# led_board.net
KiCad netlist of a schematic drawn in EAGLE
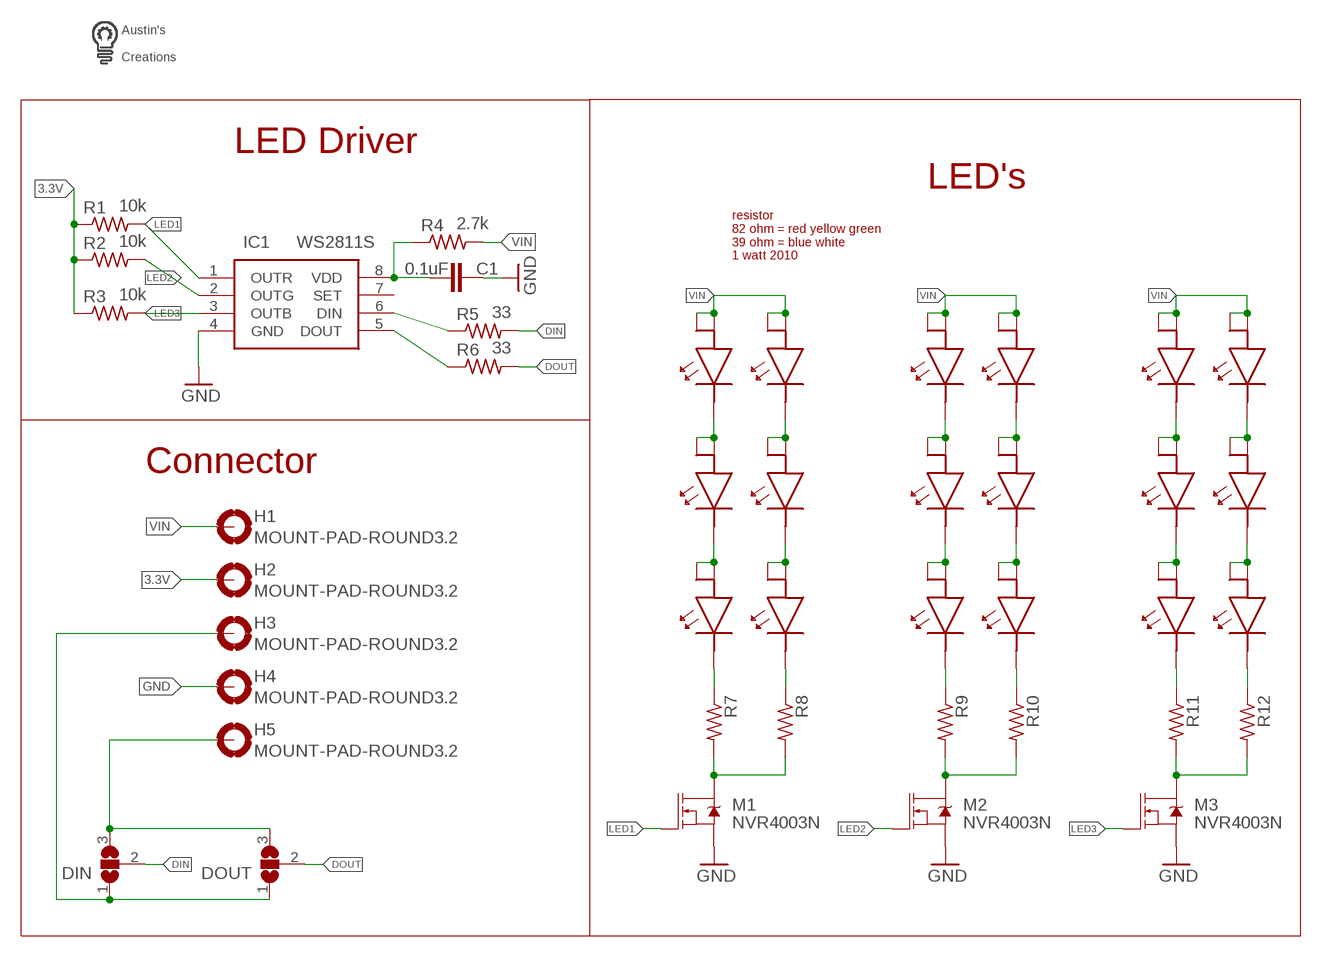
[diagram p0: schematic, sheet 1]

(export (version "E")
  (design (tool "Eeschema 10.0.6"))
  (components
    (comp (ref "C1")
      (value "0.1uF")
      (footprint "eagle-import:C0603K")
      (libsource (lib "eagle-import") (part "C-EUC0603K"))
    )
    (comp (ref "DIN")
      (value "SJ2WW")
      (footprint "eagle-import:SJ_2W")
      (libsource (lib "eagle-import") (part "SJ2WW"))
    )
    (comp (ref "DOUT")
      (value "SJ2WW")
      (footprint "eagle-import:SJ_2W")
      (libsource (lib "eagle-import") (part "SJ2WW"))
    )
    (comp (ref "H1")
      (value "MOUNT-PAD-ROUND3.2")
      (footprint "eagle-import:3,2-PAD")
      (libsource (lib "eagle-import") (part "MOUNT-PAD-ROUND3.2"))
    )
    (comp (ref "H2")
      (value "MOUNT-PAD-ROUND3.2")
      (footprint "eagle-import:3,2-PAD")
      (libsource (lib "eagle-import") (part "MOUNT-PAD-ROUND3.2"))
    )
    (comp (ref "H3")
      (value "MOUNT-PAD-ROUND3.2")
      (footprint "eagle-import:3,2-PAD")
      (libsource (lib "eagle-import") (part "MOUNT-PAD-ROUND3.2"))
    )
    (comp (ref "H4")
      (value "MOUNT-PAD-ROUND3.2")
      (footprint "eagle-import:3,2-PAD")
      (libsource (lib "eagle-import") (part "MOUNT-PAD-ROUND3.2"))
    )
    (comp (ref "H5")
      (value "MOUNT-PAD-ROUND3.2")
      (footprint "eagle-import:3,2-PAD")
      (libsource (lib "eagle-import") (part "MOUNT-PAD-ROUND3.2"))
    )
    (comp (ref "IC1")
      (value "WS2811S")
      (footprint "eagle-import:SOIC127P600X175-8N")
      (fields (field (name "MANUFACTURER_PART_NUMBER") "ws2811s"))
      (libsource (lib "eagle-import") (part "WS2811S"))
    )
    (comp (ref "L1")
      (value "5730LED")
      (footprint "eagle-import:5730LED")
      (libsource (lib "eagle-import") (part "5730LED"))
    )
    (comp (ref "L2")
      (value "5730LED")
      (footprint "eagle-import:5730LED")
      (libsource (lib "eagle-import") (part "5730LED"))
    )
    (comp (ref "L3")
      (value "5730LED")
      (footprint "eagle-import:5730LED")
      (libsource (lib "eagle-import") (part "5730LED"))
    )
    (comp (ref "L4")
      (value "5730LED")
      (footprint "eagle-import:5730LED")
      (libsource (lib "eagle-import") (part "5730LED"))
    )
    (comp (ref "L5")
      (value "5730LED")
      (footprint "eagle-import:5730LED")
      (libsource (lib "eagle-import") (part "5730LED"))
    )
    (comp (ref "L6")
      (value "5730LED")
      (footprint "eagle-import:5730LED")
      (libsource (lib "eagle-import") (part "5730LED"))
    )
    (comp (ref "L7")
      (value "5730LED")
      (footprint "eagle-import:5730LED")
      (libsource (lib "eagle-import") (part "5730LED"))
    )
    (comp (ref "L8")
      (value "5730LED")
      (footprint "eagle-import:5730LED")
      (libsource (lib "eagle-import") (part "5730LED"))
    )
    (comp (ref "L9")
      (value "5730LED")
      (footprint "eagle-import:5730LED")
      (libsource (lib "eagle-import") (part "5730LED"))
    )
    (comp (ref "L10")
      (value "5730LED")
      (footprint "eagle-import:5730LED")
      (libsource (lib "eagle-import") (part "5730LED"))
    )
    (comp (ref "L11")
      (value "5730LED")
      (footprint "eagle-import:5730LED")
      (libsource (lib "eagle-import") (part "5730LED"))
    )
    (comp (ref "L12")
      (value "5730LED")
      (footprint "eagle-import:5730LED")
      (libsource (lib "eagle-import") (part "5730LED"))
    )
    (comp (ref "L13")
      (value "5730LED")
      (footprint "eagle-import:5730LED")
      (libsource (lib "eagle-import") (part "5730LED"))
    )
    (comp (ref "L14")
      (value "5730LED")
      (footprint "eagle-import:5730LED")
      (libsource (lib "eagle-import") (part "5730LED"))
    )
    (comp (ref "L15")
      (value "5730LED")
      (footprint "eagle-import:5730LED")
      (libsource (lib "eagle-import") (part "5730LED"))
    )
    (comp (ref "L16")
      (value "5730LED")
      (footprint "eagle-import:5730LED")
      (libsource (lib "eagle-import") (part "5730LED"))
    )
    (comp (ref "L17")
      (value "5730LED")
      (footprint "eagle-import:5730LED")
      (libsource (lib "eagle-import") (part "5730LED"))
    )
    (comp (ref "L18")
      (value "5730LED")
      (footprint "eagle-import:5730LED")
      (libsource (lib "eagle-import") (part "5730LED"))
    )
    (comp (ref "M1")
      (value "NVR4003N")
      (footprint "eagle-import:SOT23")
      (libsource (lib "eagle-import") (part "NVR4003N"))
    )
    (comp (ref "M2")
      (value "NVR4003N")
      (footprint "eagle-import:SOT23")
      (libsource (lib "eagle-import") (part "NVR4003N"))
    )
    (comp (ref "M3")
      (value "NVR4003N")
      (footprint "eagle-import:SOT23")
      (libsource (lib "eagle-import") (part "NVR4003N"))
    )
    (comp (ref "R1")
      (value "10k")
      (footprint "eagle-import:R0603")
      (libsource (lib "eagle-import") (part "resistor_348_R-US_R0603"))
    )
    (comp (ref "R2")
      (value "10k")
      (footprint "eagle-import:R0603")
      (libsource (lib "eagle-import") (part "resistor_348_R-US_R0603"))
    )
    (comp (ref "R3")
      (value "10k")
      (footprint "eagle-import:R0603")
      (libsource (lib "eagle-import") (part "resistor_348_R-US_R0603"))
    )
    (comp (ref "R4")
      (value "2.7k")
      (footprint "eagle-import:R0603")
      (libsource (lib "eagle-import") (part "resistor_348_R-US_R0603"))
    )
    (comp (ref "R5")
      (value "33")
      (footprint "eagle-import:R0603")
      (libsource (lib "eagle-import") (part "resistor_348_R-US_R0603"))
    )
    (comp (ref "R6")
      (value "33")
      (footprint "eagle-import:R0603")
      (libsource (lib "eagle-import") (part "resistor_348_R-US_R0603"))
    )
    (comp (ref "R7")
      (value "R-US_R2010")
      (footprint "eagle-import:R2010")
      (libsource (lib "eagle-import") (part "R-US_R2010"))
    )
    (comp (ref "R8")
      (value "R-US_R2010")
      (footprint "eagle-import:R2010")
      (libsource (lib "eagle-import") (part "R-US_R2010"))
    )
    (comp (ref "R9")
      (value "R-US_R2010")
      (footprint "eagle-import:R2010")
      (libsource (lib "eagle-import") (part "R-US_R2010"))
    )
    (comp (ref "R10")
      (value "R-US_R2010")
      (footprint "eagle-import:R2010")
      (libsource (lib "eagle-import") (part "R-US_R2010"))
    )
    (comp (ref "R11")
      (value "R-US_R2010")
      (footprint "eagle-import:R2010")
      (libsource (lib "eagle-import") (part "R-US_R2010"))
    )
    (comp (ref "R12")
      (value "R-US_R2010")
      (footprint "eagle-import:R2010")
      (libsource (lib "eagle-import") (part "R-US_R2010"))
    )
    (comp (ref "U$2")
      (value "LOGO")
      (footprint "eagle-import:LOGO")
      (libsource (lib "eagle-import") (part "LOGO"))
    )
  )
  (nets
    (net (code "1") (name "3.3V") (class "Default")
      (node (ref "H2") (pin "B3,2") (pinfunction "MOUNT_B3,2") (pintype "passive"))
      (node (ref "R1") (pin "1") (pinfunction "1_1") (pintype "passive"))
      (node (ref "R2") (pin "1") (pinfunction "1_1") (pintype "passive"))
      (node (ref "R3") (pin "1") (pinfunction "1_1") (pintype "passive"))
    )
    (net (code "2") (name "DIN") (class "Default")
      (node (ref "DIN") (pin "2") (pinfunction "2_2") (pintype "passive"))
      (node (ref "R5") (pin "2") (pinfunction "2_2") (pintype "passive"))
    )
    (net (code "3") (name "DOUT") (class "Default")
      (node (ref "DOUT") (pin "2") (pinfunction "2_2") (pintype "passive"))
      (node (ref "R6") (pin "2") (pinfunction "2_2") (pintype "passive"))
    )
    (net (code "4") (name "GND") (class "Default")
      (node (ref "C1") (pin "1") (pinfunction "1_1") (pintype "passive"))
      (node (ref "H4") (pin "B3,2") (pinfunction "MOUNT_B3,2") (pintype "passive"))
      (node (ref "IC1") (pin "4") (pinfunction "GND_4") (pintype "power_in"))
      (node (ref "M1") (pin "3") (pinfunction "S_3") (pintype "bidirectional"))
      (node (ref "M2") (pin "3") (pinfunction "S_3") (pintype "bidirectional"))
      (node (ref "M3") (pin "3") (pinfunction "S_3") (pintype "bidirectional"))
    )
    (net (code "5") (name "LED1") (class "Default")
      (node (ref "IC1") (pin "1") (pinfunction "OUTR_1") (pintype "output"))
      (node (ref "M1") (pin "2") (pinfunction "G_2") (pintype "bidirectional"))
      (node (ref "R1") (pin "2") (pinfunction "2_2") (pintype "passive"))
    )
    (net (code "6") (name "LED2") (class "Default")
      (node (ref "IC1") (pin "2") (pinfunction "OUTG_2") (pintype "output"))
      (node (ref "M2") (pin "2") (pinfunction "G_2") (pintype "bidirectional"))
      (node (ref "R2") (pin "2") (pinfunction "2_2") (pintype "passive"))
    )
    (net (code "7") (name "LED3") (class "Default")
      (node (ref "IC1") (pin "3") (pinfunction "OUTB_3") (pintype "output"))
      (node (ref "M3") (pin "2") (pinfunction "G_2") (pintype "bidirectional"))
      (node (ref "R3") (pin "2") (pinfunction "2_2") (pintype "passive"))
    )
    (net (code "8") (name "Net-(H3-MOUNT)") (class "Default")
      (node (ref "DIN") (pin "1") (pinfunction "1_1") (pintype "passive"))
      (node (ref "DOUT") (pin "1") (pinfunction "1_1") (pintype "passive"))
      (node (ref "H3") (pin "B3,2") (pinfunction "MOUNT_B3,2") (pintype "passive"))
    )
    (net (code "9") (name "Net-(H5-MOUNT)") (class "Default")
      (node (ref "DIN") (pin "3") (pinfunction "3_3") (pintype "passive"))
      (node (ref "DOUT") (pin "3") (pinfunction "3_3") (pintype "passive"))
      (node (ref "H5") (pin "B3,2") (pinfunction "MOUNT_B3,2") (pintype "passive"))
    )
    (net (code "10") (name "Net-(IC1-DIN)") (class "Default")
      (node (ref "IC1") (pin "6") (pinfunction "DIN_6") (pintype "input"))
      (node (ref "R5") (pin "1") (pinfunction "1_1") (pintype "passive"))
    )
    (net (code "11") (name "Net-(IC1-DOUT)") (class "Default")
      (node (ref "IC1") (pin "5") (pinfunction "DOUT_5") (pintype "bidirectional"))
      (node (ref "R6") (pin "1") (pinfunction "1_1") (pintype "passive"))
    )
    (net (code "12") (name "Net-(IC1-VDD)") (class "Default")
      (node (ref "C1") (pin "2") (pinfunction "2_2") (pintype "passive"))
      (node (ref "IC1") (pin "8") (pinfunction "VDD_8") (pintype "power_in"))
      (node (ref "R4") (pin "1") (pinfunction "1_1") (pintype "passive"))
    )
    (net (code "13") (name "Net-(L1-PadP$2)") (class "Default")
      (node (ref "L1") (pin "P$2") (pinfunction "P$2_P$2") (pintype "bidirectional"))
      (node (ref "L2") (pin "P$1") (pinfunction "P$1_P$1") (pintype "bidirectional"))
      (node (ref "L2") (pin "P$3") (pinfunction "P$3_P$3") (pintype "bidirectional"))
    )
    (net (code "14") (name "Net-(L2-PadP$2)") (class "Default")
      (node (ref "L2") (pin "P$2") (pinfunction "P$2_P$2") (pintype "bidirectional"))
      (node (ref "L3") (pin "P$1") (pinfunction "P$1_P$1") (pintype "bidirectional"))
      (node (ref "L3") (pin "P$3") (pinfunction "P$3_P$3") (pintype "bidirectional"))
    )
    (net (code "15") (name "Net-(L3-PadP$2)") (class "Default")
      (node (ref "L3") (pin "P$2") (pinfunction "P$2_P$2") (pintype "bidirectional"))
      (node (ref "R7") (pin "1") (pinfunction "1_1") (pintype "passive"))
    )
    (net (code "16") (name "Net-(L4-PadP$2)") (class "Default")
      (node (ref "L4") (pin "P$2") (pinfunction "P$2_P$2") (pintype "bidirectional"))
      (node (ref "L5") (pin "P$1") (pinfunction "P$1_P$1") (pintype "bidirectional"))
      (node (ref "L5") (pin "P$3") (pinfunction "P$3_P$3") (pintype "bidirectional"))
    )
    (net (code "17") (name "Net-(L5-PadP$2)") (class "Default")
      (node (ref "L5") (pin "P$2") (pinfunction "P$2_P$2") (pintype "bidirectional"))
      (node (ref "L6") (pin "P$1") (pinfunction "P$1_P$1") (pintype "bidirectional"))
      (node (ref "L6") (pin "P$3") (pinfunction "P$3_P$3") (pintype "bidirectional"))
    )
    (net (code "18") (name "Net-(L6-PadP$2)") (class "Default")
      (node (ref "L6") (pin "P$2") (pinfunction "P$2_P$2") (pintype "bidirectional"))
      (node (ref "R8") (pin "1") (pinfunction "1_1") (pintype "passive"))
    )
    (net (code "19") (name "Net-(L7-PadP$2)") (class "Default")
      (node (ref "L7") (pin "P$2") (pinfunction "P$2_P$2") (pintype "bidirectional"))
      (node (ref "L8") (pin "P$1") (pinfunction "P$1_P$1") (pintype "bidirectional"))
      (node (ref "L8") (pin "P$3") (pinfunction "P$3_P$3") (pintype "bidirectional"))
    )
    (net (code "20") (name "Net-(L8-PadP$2)") (class "Default")
      (node (ref "L8") (pin "P$2") (pinfunction "P$2_P$2") (pintype "bidirectional"))
      (node (ref "L9") (pin "P$1") (pinfunction "P$1_P$1") (pintype "bidirectional"))
      (node (ref "L9") (pin "P$3") (pinfunction "P$3_P$3") (pintype "bidirectional"))
    )
    (net (code "21") (name "Net-(L9-PadP$2)") (class "Default")
      (node (ref "L9") (pin "P$2") (pinfunction "P$2_P$2") (pintype "bidirectional"))
      (node (ref "R9") (pin "1") (pinfunction "1_1") (pintype "passive"))
    )
    (net (code "22") (name "Net-(L10-PadP$2)") (class "Default")
      (node (ref "L10") (pin "P$2") (pinfunction "P$2_P$2") (pintype "bidirectional"))
      (node (ref "L11") (pin "P$1") (pinfunction "P$1_P$1") (pintype "bidirectional"))
      (node (ref "L11") (pin "P$3") (pinfunction "P$3_P$3") (pintype "bidirectional"))
    )
    (net (code "23") (name "Net-(L11-PadP$2)") (class "Default")
      (node (ref "L11") (pin "P$2") (pinfunction "P$2_P$2") (pintype "bidirectional"))
      (node (ref "L12") (pin "P$1") (pinfunction "P$1_P$1") (pintype "bidirectional"))
      (node (ref "L12") (pin "P$3") (pinfunction "P$3_P$3") (pintype "bidirectional"))
    )
    (net (code "24") (name "Net-(L12-PadP$2)") (class "Default")
      (node (ref "L12") (pin "P$2") (pinfunction "P$2_P$2") (pintype "bidirectional"))
      (node (ref "R10") (pin "1") (pinfunction "1_1") (pintype "passive"))
    )
    (net (code "25") (name "Net-(L13-PadP$2)") (class "Default")
      (node (ref "L13") (pin "P$2") (pinfunction "P$2_P$2") (pintype "bidirectional"))
      (node (ref "L14") (pin "P$1") (pinfunction "P$1_P$1") (pintype "bidirectional"))
      (node (ref "L14") (pin "P$3") (pinfunction "P$3_P$3") (pintype "bidirectional"))
    )
    (net (code "26") (name "Net-(L14-PadP$2)") (class "Default")
      (node (ref "L14") (pin "P$2") (pinfunction "P$2_P$2") (pintype "bidirectional"))
      (node (ref "L15") (pin "P$1") (pinfunction "P$1_P$1") (pintype "bidirectional"))
      (node (ref "L15") (pin "P$3") (pinfunction "P$3_P$3") (pintype "bidirectional"))
    )
    (net (code "27") (name "Net-(L15-PadP$2)") (class "Default")
      (node (ref "L15") (pin "P$2") (pinfunction "P$2_P$2") (pintype "bidirectional"))
      (node (ref "R11") (pin "1") (pinfunction "1_1") (pintype "passive"))
    )
    (net (code "28") (name "Net-(L16-PadP$2)") (class "Default")
      (node (ref "L16") (pin "P$2") (pinfunction "P$2_P$2") (pintype "bidirectional"))
      (node (ref "L17") (pin "P$1") (pinfunction "P$1_P$1") (pintype "bidirectional"))
      (node (ref "L17") (pin "P$3") (pinfunction "P$3_P$3") (pintype "bidirectional"))
    )
    (net (code "29") (name "Net-(L17-PadP$2)") (class "Default")
      (node (ref "L17") (pin "P$2") (pinfunction "P$2_P$2") (pintype "bidirectional"))
      (node (ref "L18") (pin "P$1") (pinfunction "P$1_P$1") (pintype "bidirectional"))
      (node (ref "L18") (pin "P$3") (pinfunction "P$3_P$3") (pintype "bidirectional"))
    )
    (net (code "30") (name "Net-(L18-PadP$2)") (class "Default")
      (node (ref "L18") (pin "P$2") (pinfunction "P$2_P$2") (pintype "bidirectional"))
      (node (ref "R12") (pin "1") (pinfunction "1_1") (pintype "passive"))
    )
    (net (code "31") (name "Net-(M1-D)") (class "Default")
      (node (ref "M1") (pin "1") (pinfunction "D_1") (pintype "bidirectional"))
      (node (ref "R7") (pin "2") (pinfunction "2_2") (pintype "passive"))
      (node (ref "R8") (pin "2") (pinfunction "2_2") (pintype "passive"))
    )
    (net (code "32") (name "Net-(M2-D)") (class "Default")
      (node (ref "M2") (pin "1") (pinfunction "D_1") (pintype "bidirectional"))
      (node (ref "R10") (pin "2") (pinfunction "2_2") (pintype "passive"))
      (node (ref "R9") (pin "2") (pinfunction "2_2") (pintype "passive"))
    )
    (net (code "33") (name "Net-(M3-D)") (class "Default")
      (node (ref "M3") (pin "1") (pinfunction "D_1") (pintype "bidirectional"))
      (node (ref "R11") (pin "2") (pinfunction "2_2") (pintype "passive"))
      (node (ref "R12") (pin "2") (pinfunction "2_2") (pintype "passive"))
    )
    (net (code "34") (name "VIN") (class "Default")
      (node (ref "H1") (pin "B3,2") (pinfunction "MOUNT_B3,2") (pintype "passive"))
      (node (ref "L1") (pin "P$1") (pinfunction "P$1_P$1") (pintype "bidirectional"))
      (node (ref "L1") (pin "P$3") (pinfunction "P$3_P$3") (pintype "bidirectional"))
      (node (ref "L10") (pin "P$1") (pinfunction "P$1_P$1") (pintype "bidirectional"))
      (node (ref "L10") (pin "P$3") (pinfunction "P$3_P$3") (pintype "bidirectional"))
      (node (ref "L13") (pin "P$1") (pinfunction "P$1_P$1") (pintype "bidirectional"))
      (node (ref "L13") (pin "P$3") (pinfunction "P$3_P$3") (pintype "bidirectional"))
      (node (ref "L16") (pin "P$1") (pinfunction "P$1_P$1") (pintype "bidirectional"))
      (node (ref "L16") (pin "P$3") (pinfunction "P$3_P$3") (pintype "bidirectional"))
      (node (ref "L4") (pin "P$1") (pinfunction "P$1_P$1") (pintype "bidirectional"))
      (node (ref "L4") (pin "P$3") (pinfunction "P$3_P$3") (pintype "bidirectional"))
      (node (ref "L7") (pin "P$1") (pinfunction "P$1_P$1") (pintype "bidirectional"))
      (node (ref "L7") (pin "P$3") (pinfunction "P$3_P$3") (pintype "bidirectional"))
      (node (ref "R4") (pin "2") (pinfunction "2_2") (pintype "passive"))
    )
    (net (code "35") (name "unconnected-(IC1-SET-Pad7)") (class "Default")
      (node (ref "IC1") (pin "7") (pinfunction "SET_7") (pintype "input"))
    )
  )
)
